# fasciaMainBoard_V0_1.net
KiCad netlist of a schematic drawn in EAGLE
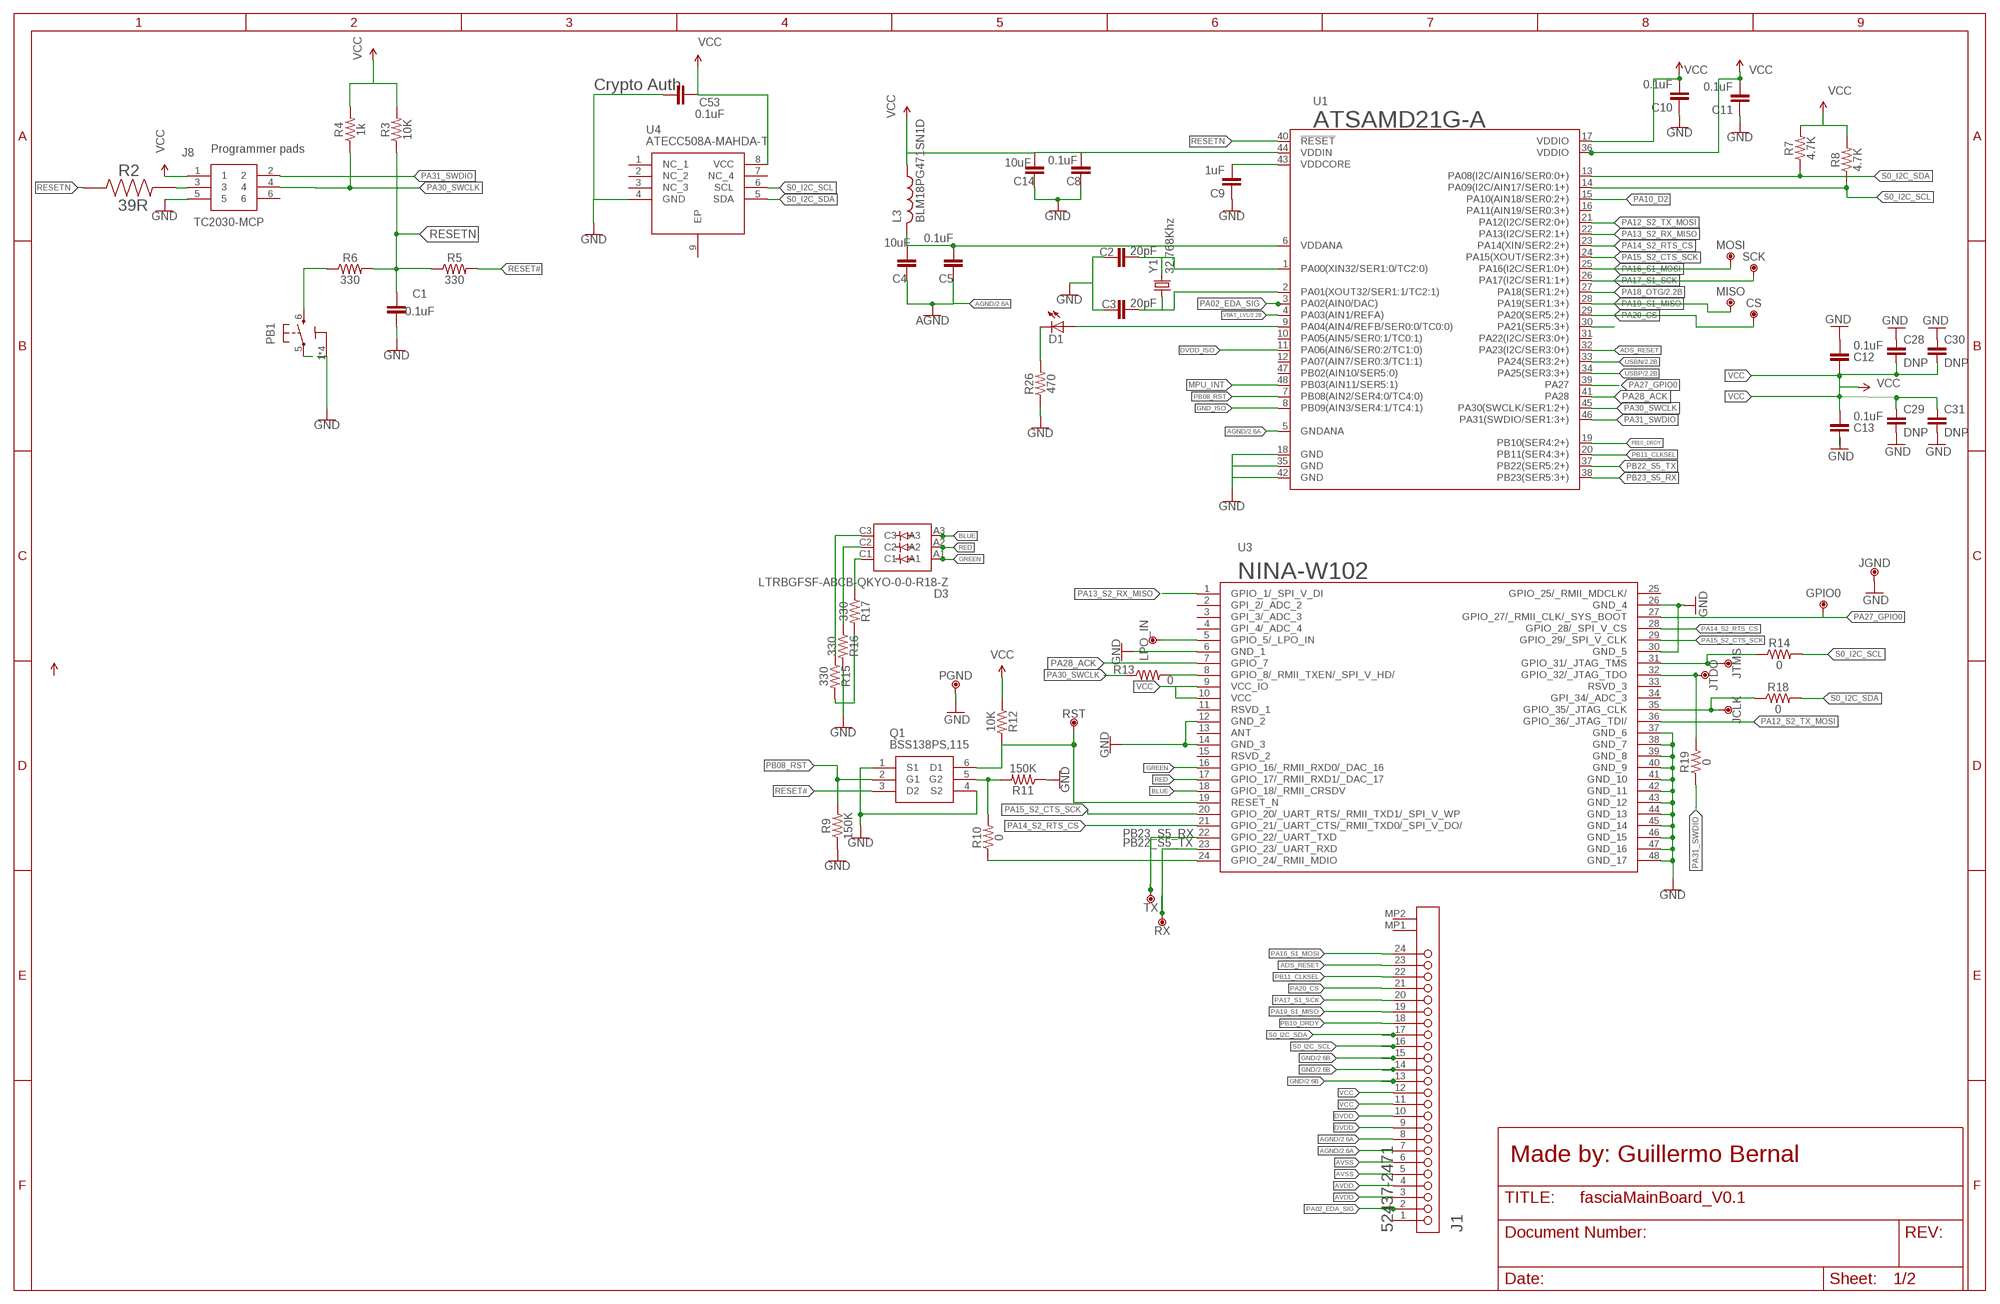
[diagram p0: schematic, sheet 1]
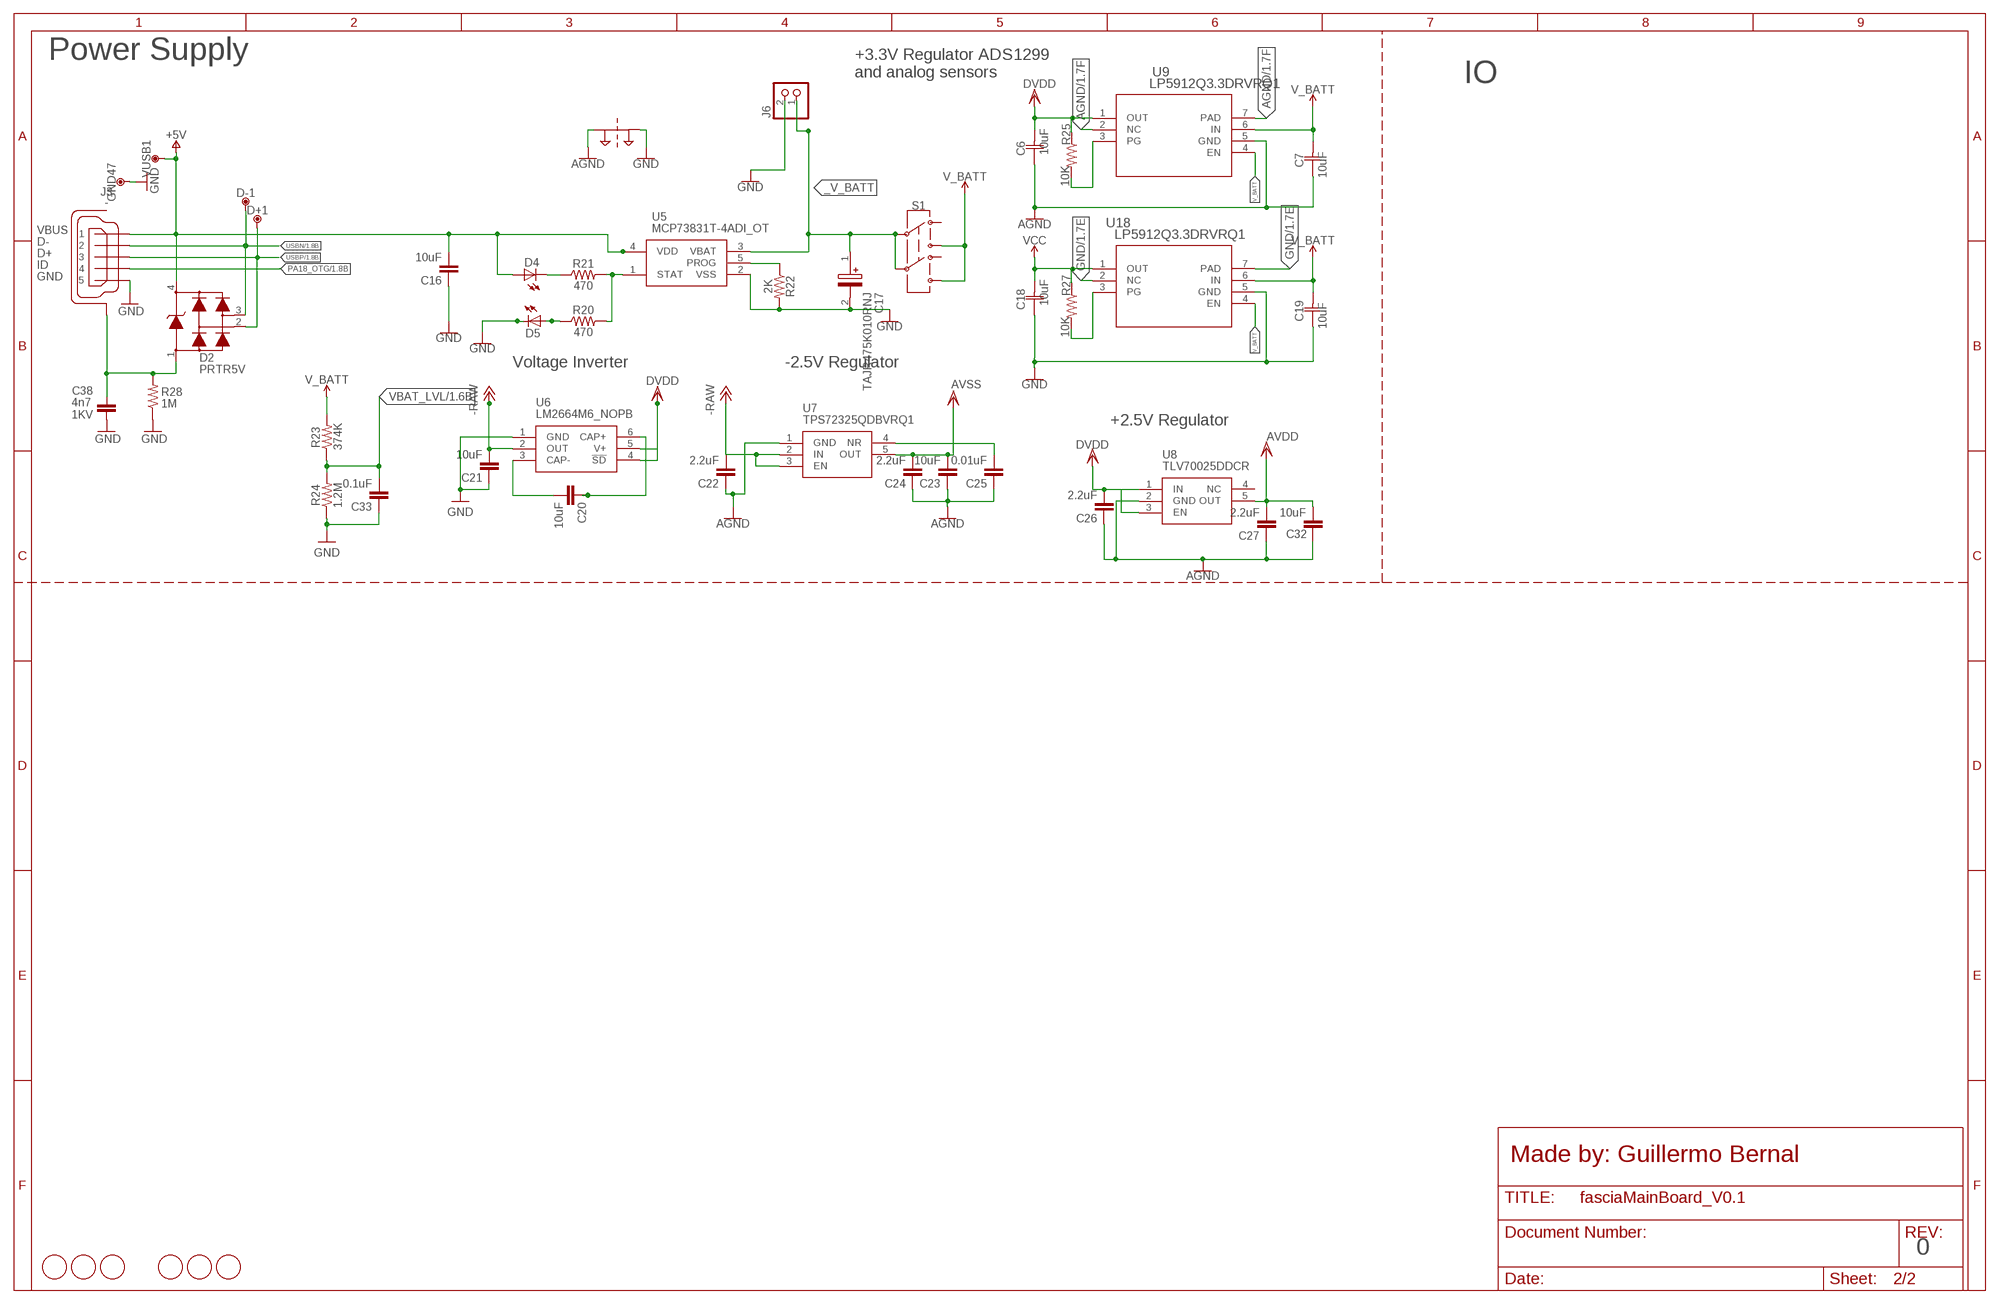
[diagram p1: schematic, sheet 2]

(export (version "E")
  (design (tool "Eeschema 10.0.6"))
  (components
    (comp (ref "C1")
      (value "0.1uF")
      (footprint "eagle-import:0402-TIGHT")
      (libsource (lib "eagle-import") (part "0.1UF-0402T-16V-10%"))
    )
    (comp (ref "C2")
      (value "20pF")
      (footprint "eagle-import:0402-TIGHT")
      (libsource (lib "eagle-import") (part "20PF-0402T-16V-10%"))
    )
    (comp (ref "C3")
      (value "20pF")
      (footprint "eagle-import:0402-TIGHT")
      (libsource (lib "eagle-import") (part "20PF-0402T-16V-10%"))
    )
    (comp (ref "C4")
      (value "10uF")
      (footprint "eagle-import:0603")
      (libsource (lib "eagle-import") (part "SparkFun-Capacitors_510_10UF-0603-6.3V-20%"))
    )
    (comp (ref "C5")
      (value "0.1uF")
      (footprint "eagle-import:0402-TIGHT")
      (libsource (lib "eagle-import") (part "0.1UF-0402T-16V-10%"))
    )
    (comp (ref "C8")
      (value "0.1uF")
      (footprint "eagle-import:0402-TIGHT")
      (libsource (lib "eagle-import") (part "0.1UF-0402T-16V-10%"))
    )
    (comp (ref "C9")
      (value "1uF")
      (footprint "eagle-import:0402-TIGHT")
      (libsource (lib "eagle-import") (part "1UF-0402T-16V-10%"))
    )
    (comp (ref "C10")
      (value "0.1uF")
      (footprint "eagle-import:0402-TIGHT")
      (libsource (lib "eagle-import") (part "0.1UF-0402T-16V-10%"))
    )
    (comp (ref "C11")
      (value "0.1uF")
      (footprint "eagle-import:0402-TIGHT")
      (libsource (lib "eagle-import") (part "0.1UF-0402T-16V-10%"))
    )
    (comp (ref "C12")
      (value "0.1uF")
      (footprint "eagle-import:0402-TIGHT")
      (libsource (lib "eagle-import") (part "0.1UF-0402T-16V-10%"))
    )
    (comp (ref "C13")
      (value "0.1uF")
      (footprint "eagle-import:0402-TIGHT")
      (libsource (lib "eagle-import") (part "0.1UF-0402T-16V-10%"))
    )
    (comp (ref "C14")
      (value "10uF")
      (footprint "eagle-import:0603")
      (libsource (lib "eagle-import") (part "SparkFun-Capacitors_510_10UF-0603-6.3V-20%"))
    )
    (comp (ref "C28")
      (value "DNP")
      (footprint "eagle-import:0402-1005X55N")
      (libsource (lib "eagle-import") (part "C-0402DNP"))
    )
    (comp (ref "C29")
      (value "DNP")
      (footprint "eagle-import:0402-1005X55N")
      (libsource (lib "eagle-import") (part "C-0402DNP"))
    )
    (comp (ref "C30")
      (value "DNP")
      (footprint "eagle-import:0603-1608X90N")
      (libsource (lib "eagle-import") (part "C-0603-DNP"))
    )
    (comp (ref "C31")
      (value "DNP")
      (footprint "eagle-import:0603-1608X90N")
      (libsource (lib "eagle-import") (part "C-0603-DNP"))
    )
    (comp (ref "C53")
      (value "0.1uF")
      (footprint "eagle-import:0402-TIGHT")
      (libsource (lib "eagle-import") (part "0.1UF-0402T-16V-10%"))
    )
    (comp (ref "CS")
      (value "DNP")
      (footprint "eagle-import:TP-0.8MM")
      (libsource (lib "eagle-import") (part "TPTP-0.8MM"))
    )
    (comp (ref "D1")
      (value "LEDCHIPLED_0603")
      (footprint "eagle-import:CHIPLED_0603")
      (libsource (lib "eagle-import") (part "LEDCHIPLED_0603"))
    )
    (comp (ref "D3")
      (value "LTRBGFSF-ABCB-QKYO-0-0-R18-Z")
      (footprint "eagle-import:PLCC-6")
      (libsource (lib "eagle-import") (part "LTRBGFSF-ABCB-QKYO-0-0-R18-Z"))
    )
    (comp (ref "GPIO0")
      (value "DNP")
      (footprint "eagle-import:TP-0.8MM")
      (libsource (lib "eagle-import") (part "TPTP-0.8MM"))
    )
    (comp (ref "J1")
      (value "MOLEX_52437-2471MOLEX_52437-2471_0_0")
      (footprint "eagle-import:MOLEX_52437-2471_0")
      (fields (field (name "MF") "Molex") (field (name "MPN") "52437-2471"))
      (libsource (lib "eagle-import") (part "MOLEX_52437-2471MOLEX_52437-2471_0_0"))
    )
    (comp (ref "J8")
      (value "TC2030-MCP")
      (footprint "eagle-import:TC2030MCP")
      (fields (field (name "MOUSER_PART_NUMBER") "579-TC2030-MCP") (field (name "RS_PART_NUMBER") "8252568"))
      (libsource (lib "eagle-import") (part "TC2030-MCP"))
    )
    (comp (ref "JCLK")
      (value "DNP")
      (footprint "eagle-import:TP-0.8MM")
      (libsource (lib "eagle-import") (part "TPTP-0.8MM"))
    )
    (comp (ref "JGND")
      (value "DNP")
      (footprint "eagle-import:TP-0.8MM")
      (libsource (lib "eagle-import") (part "TPTP-0.8MM"))
    )
    (comp (ref "JTDO")
      (value "DNP")
      (footprint "eagle-import:TP-0.8MM")
      (libsource (lib "eagle-import") (part "TPTP-0.8MM"))
    )
    (comp (ref "JTMS")
      (value "DNP")
      (footprint "eagle-import:TP-0.8MM")
      (libsource (lib "eagle-import") (part "TPTP-0.8MM"))
    )
    (comp (ref "L3")
      (value "BLM18PG471SN1D")
      (footprint "eagle-import:BEADC1608X95N")
      (fields
        (field (name "MOUSER_PART_NUMBER") "81-BLM18PG471SN1D")
        (field (name "RS_PART_NUMBER") "7241425P")
      )
      (libsource (lib "eagle-import") (part "BLM18PG471SN1D"))
    )
    (comp (ref "LPO_IN")
      (value "DNP")
      (footprint "eagle-import:TP-0.8MM")
      (libsource (lib "eagle-import") (part "TPTP-0.8MM"))
    )
    (comp (ref "MISO")
      (value "DNP")
      (footprint "eagle-import:TP-0.8MM")
      (libsource (lib "eagle-import") (part "TPTP-0.8MM"))
    )
    (comp (ref "MOSI")
      (value "DNP")
      (footprint "eagle-import:TP-0.8MM")
      (libsource (lib "eagle-import") (part "TPTP-0.8MM"))
    )
    (comp (ref "PB1")
      (value "PTS820")
      (footprint "eagle-import:C&K_PTS820_NO_HOLES")
      (fields (field (name "MANUFACTURER") "C&K"))
      (libsource (lib "eagle-import") (part "TACTILE1PTS820-NH"))
    )
    (comp (ref "PGND")
      (value "DNP")
      (footprint "eagle-import:TP-0.8MM")
      (libsource (lib "eagle-import") (part "TPTP-0.8MM"))
    )
    (comp (ref "Q1")
      (value "BSS138PS,115")
      (footprint "eagle-import:SOT65P210X110-6N")
      (fields
        (field (name "MOUSER_PART_NUMBER") "771-BSS138PS115")
        (field (name "RS_PART_NUMBER") "7920901P")
      )
      (libsource (lib "eagle-import") (part "BSS138PS,115"))
    )
    (comp (ref "R2")
      (value "39R")
      (footprint "eagle-import:RESC1005X40N")
      (fields (field (name "MF") "Yageo") (field (name "MP") "RC0402FR-0739RL"))
      (libsource (lib "eagle-import") (part "RC0402FR-0739RL"))
    )
    (comp (ref "R3")
      (value "10K")
      (footprint "eagle-import:0402-TIGHT")
      (libsource (lib "eagle-import") (part "10K"))
    )
    (comp (ref "R4")
      (value "1k")
      (footprint "eagle-import:0402-TIGHT")
      (libsource (lib "eagle-import") (part "1K"))
    )
    (comp (ref "R5")
      (value "330")
      (footprint "eagle-import:0402-TIGHT")
      (libsource (lib "eagle-import") (part "330"))
    )
    (comp (ref "R6")
      (value "330")
      (footprint "eagle-import:0402-TIGHT")
      (libsource (lib "eagle-import") (part "330"))
    )
    (comp (ref "R7")
      (value "4.7K")
      (footprint "eagle-import:0402-TIGHT")
      (libsource (lib "eagle-import") (part "4.7K"))
    )
    (comp (ref "R8")
      (value "4.7K")
      (footprint "eagle-import:0402-TIGHT")
      (libsource (lib "eagle-import") (part "4.7K"))
    )
    (comp (ref "R9")
      (value "150K")
      (footprint "eagle-import:0402-TIGHT")
      (libsource (lib "eagle-import") (part "100K"))
    )
    (comp (ref "R10")
      (value "0")
      (footprint "eagle-import:0402-TIGHT")
      (libsource (lib "eagle-import") (part "0"))
    )
    (comp (ref "R11")
      (value "150K")
      (footprint "eagle-import:0402-TIGHT")
      (libsource (lib "eagle-import") (part "100K"))
    )
    (comp (ref "R12")
      (value "10K")
      (footprint "eagle-import:0402-TIGHT")
      (libsource (lib "eagle-import") (part "10K"))
    )
    (comp (ref "R13")
      (value "0")
      (footprint "eagle-import:0402-TIGHT")
      (libsource (lib "eagle-import") (part "0"))
    )
    (comp (ref "R14")
      (value "0")
      (footprint "eagle-import:0402-TIGHT")
      (libsource (lib "eagle-import") (part "0"))
    )
    (comp (ref "R15")
      (value "330")
      (footprint "eagle-import:0402-TIGHT")
      (libsource (lib "eagle-import") (part "330"))
    )
    (comp (ref "R16")
      (value "330")
      (footprint "eagle-import:0402-TIGHT")
      (libsource (lib "eagle-import") (part "330"))
    )
    (comp (ref "R17")
      (value "330")
      (footprint "eagle-import:0402-TIGHT")
      (libsource (lib "eagle-import") (part "330"))
    )
    (comp (ref "R18")
      (value "0")
      (footprint "eagle-import:0402-TIGHT")
      (libsource (lib "eagle-import") (part "0"))
    )
    (comp (ref "R19")
      (value "0")
      (footprint "eagle-import:0402-TIGHT")
      (libsource (lib "eagle-import") (part "0"))
    )
    (comp (ref "R26")
      (value "470")
      (footprint "eagle-import:0402-TIGHT")
      (libsource (lib "eagle-import") (part "470"))
    )
    (comp (ref "RST")
      (value "DNP")
      (footprint "eagle-import:TP-0.8MM")
      (libsource (lib "eagle-import") (part "TPTP-0.8MM"))
    )
    (comp (ref "RX")
      (value "DNP")
      (footprint "eagle-import:TP-0.8MM")
      (libsource (lib "eagle-import") (part "TPTP-0.8MM"))
    )
    (comp (ref "SCK")
      (value "DNP")
      (footprint "eagle-import:TP-0.8MM")
      (libsource (lib "eagle-import") (part "TPTP-0.8MM"))
    )
    (comp (ref "TX")
      (value "DNP")
      (footprint "eagle-import:TP-0.8MM")
      (libsource (lib "eagle-import") (part "TPTP-0.8MM"))
    )
    (comp (ref "U1")
      (value "ATSAMD21G-A")
      (footprint "eagle-import:TQFP-48")
      (libsource (lib "eagle-import") (part "ATSAMD21G-A"))
    )
    (comp (ref "U3")
      (value "NINA-W102")
      (footprint "eagle-import:NINAW102")
      (libsource (lib "eagle-import") (part "NINA-W102"))
    )
    (comp (ref "U4")
      (value "ATECC508A-MAHDA-T")
      (footprint "eagle-import:SON50P300X200X60-9N")
      (fields
        (field (name "MOUSER_PART_NUMBER") "556-ATECC508A-MAHDAT")
        (field (name "RS_PART_NUMBER") "1773144P")
      )
      (libsource (lib "eagle-import") (part "ATECC508A-MAHDA-T"))
    )
    (comp (ref "Y1")
      (value "32.768Khz")
      (footprint "eagle-import:ECX-31B")
      (fields
        (field (name "MANUFACTURER_PART_NUMBER") "ECS-.327-12.5-34B-TR")
        (field (name "MOUSER_PART_NUMBER") "520-327-12.5-34B")
      )
      (libsource (lib "eagle-import") (part "ECS-.327-12.5-34B-TR"))
    )
    (comp (ref "C6")
      (value "10uF")
      (footprint "eagle-import:CAP_CL10-L")
      (fields (field (name "MANUFACTURER_PART_NUMBER") "CL10B106MQ8NRNC"))
      (libsource (lib "eagle-import") (part "CL10B106MQ8NRNCCAP_CL10-L"))
    )
    (comp (ref "C7")
      (value "10uF")
      (footprint "eagle-import:CAP_CL10-L")
      (fields (field (name "MANUFACTURER_PART_NUMBER") "CL10B106MQ8NRNC"))
      (libsource (lib "eagle-import") (part "CL10B106MQ8NRNCCAP_CL10-L"))
    )
    (comp (ref "C16")
      (value "10uF")
      (footprint "eagle-import:0603")
      (libsource (lib "eagle-import") (part "10UF-0603-6.3V-20%"))
    )
    (comp (ref "C17")
      (value "TAJR475K010RNJ")
      (footprint "eagle-import:CAPPM2014X120N")
      (fields
        (field (name "MOUSER_PART_NUMBER") "581-TAJR475K010R")
        (field (name "RS_PART_NUMBER") "1355409P")
      )
      (libsource (lib "eagle-import") (part "TAJR475K010RNJ"))
    )
    (comp (ref "C18")
      (value "10uF")
      (footprint "eagle-import:CAP_CL10-L")
      (fields (field (name "MANUFACTURER_PART_NUMBER") "CL10B106MQ8NRNC"))
      (libsource (lib "eagle-import") (part "CL10B106MQ8NRNCCAP_CL10-L"))
    )
    (comp (ref "C19")
      (value "10uF")
      (footprint "eagle-import:CAP_CL10-L")
      (fields (field (name "MANUFACTURER_PART_NUMBER") "CL10B106MQ8NRNC"))
      (libsource (lib "eagle-import") (part "CL10B106MQ8NRNCCAP_CL10-L"))
    )
    (comp (ref "C20")
      (value "10uF")
      (footprint "eagle-import:0603")
      (libsource (lib "eagle-import") (part "10UF-0603-6.3V-20%"))
    )
    (comp (ref "C21")
      (value "10uF")
      (footprint "eagle-import:0603")
      (libsource (lib "eagle-import") (part "10UF-0603-6.3V-20%"))
    )
    (comp (ref "C22")
      (value "2.2uF")
      (footprint "eagle-import:0402-TIGHT")
      (libsource (lib "eagle-import") (part "2.2UF-0402T-16V-10%"))
    )
    (comp (ref "C23")
      (value "10uF")
      (footprint "eagle-import:0603")
      (libsource (lib "eagle-import") (part "10UF-0603-6.3V-20%"))
    )
    (comp (ref "C24")
      (value "2.2uF")
      (footprint "eagle-import:0402-TIGHT")
      (libsource (lib "eagle-import") (part "2.2UF-0402T-16V-10%"))
    )
    (comp (ref "C25")
      (value "0.01uF")
      (footprint "eagle-import:0402-TIGHT")
      (libsource (lib "eagle-import") (part "0.01UF-0402T-16V-10%"))
    )
    (comp (ref "C26")
      (value "2.2uF")
      (footprint "eagle-import:0402-TIGHT")
      (libsource (lib "eagle-import") (part "2.2UF-0402T-16V-10%"))
    )
    (comp (ref "C27")
      (value "2.2uF")
      (footprint "eagle-import:0402-TIGHT")
      (libsource (lib "eagle-import") (part "2.2UF-0402T-16V-10%"))
    )
    (comp (ref "C32")
      (value "10uF")
      (footprint "eagle-import:0603")
      (libsource (lib "eagle-import") (part "10UF-0603-6.3V-20%"))
    )
    (comp (ref "C33")
      (value "0.1uF")
      (footprint "eagle-import:0402-TIGHT")
      (libsource (lib "eagle-import") (part "0.1UF-0402T-16V-10%"))
    )
    (comp (ref "C38")
      (value "4n7")
      (footprint "eagle-import:0805-R2013X50N")
      (fields (field (name "MANUFACTURER") "Kemet") (field (name "VOLTAGE") "1KV"))
      (libsource (lib "eagle-import") (part "C-08054.7NF"))
    )
    (comp (ref "D+1")
      (value "DNP")
      (footprint "eagle-import:TP-1.00MM")
      (libsource (lib "eagle-import") (part "TPTP-1.00MM"))
    )
    (comp (ref "D-1")
      (value "DNP")
      (footprint "eagle-import:TP-1.00MM")
      (libsource (lib "eagle-import") (part "TPTP-1.00MM"))
    )
    (comp (ref "D2")
      (value "PRTR5V")
      (footprint "eagle-import:SOT190P230X110-4N")
      (fields (field (name "MANUFACTURER") "NXP"))
      (libsource (lib "eagle-import") (part "PRTR5V0U2X,215"))
    )
    (comp (ref "D4")
      (value "LEDCHIPLED_0603")
      (footprint "eagle-import:CHIPLED_0603")
      (libsource (lib "eagle-import") (part "LEDCHIPLED_0603"))
    )
    (comp (ref "D5")
      (value "LEDCHIPLED_0603")
      (footprint "eagle-import:CHIPLED_0603")
      (libsource (lib "eagle-import") (part "LEDCHIPLED_0603"))
    )
    (comp (ref "FD1")
      (value "DNP")
      (footprint "eagle-import:FD-1-1.5")
      (libsource (lib "eagle-import") (part "FIDUCIAL-1.5MM"))
    )
    (comp (ref "FD2")
      (value "DNP")
      (footprint "eagle-import:FD-1-1.5")
      (libsource (lib "eagle-import") (part "FIDUCIAL-1.5MM"))
    )
    (comp (ref "FD3")
      (value "DNP")
      (footprint "eagle-import:FD-1-1.5")
      (libsource (lib "eagle-import") (part "FIDUCIAL-1.5MM"))
    )
    (comp (ref "FD4")
      (value "DNP")
      (footprint "eagle-import:FD-1-1.5")
      (libsource (lib "eagle-import") (part "FIDUCIAL-1.5MM"))
    )
    (comp (ref "FD5")
      (value "DNP")
      (footprint "eagle-import:FD-1-1.5")
      (libsource (lib "eagle-import") (part "FIDUCIAL-1.5MM"))
    )
    (comp (ref "FD6")
      (value "DNP")
      (footprint "eagle-import:FD-1-1.5")
      (libsource (lib "eagle-import") (part "FIDUCIAL-1.5MM"))
    )
    (comp (ref "GND47")
      (value "DNP")
      (footprint "eagle-import:TP-1.00MM")
      (libsource (lib "eagle-import") (part "TPTP-1.00MM"))
    )
    (comp (ref "J3")
      (value "-")
      (footprint "eagle-import:ZX62-AB-5PA")
      (fields (field (name "MANUFACTURER") "Hirose"))
      (libsource (lib "eagle-import") (part "USB-MICRO"))
    )
    (comp (ref "J6")
      (value "JST_2PIN-SMT-RA")
      (footprint "eagle-import:JST-PH-2-SMT-RA")
      (libsource (lib "eagle-import") (part "JST_2PIN-SMT-RA"))
    )
    (comp (ref "R20")
      (value "470")
      (footprint "eagle-import:0402-TIGHT")
      (libsource (lib "eagle-import") (part "470"))
    )
    (comp (ref "R21")
      (value "470")
      (footprint "eagle-import:0402-TIGHT")
      (libsource (lib "eagle-import") (part "470"))
    )
    (comp (ref "R22")
      (value "2K")
      (footprint "eagle-import:0402-TIGHT")
      (libsource (lib "eagle-import") (part "2K"))
    )
    (comp (ref "R23")
      (value "374K")
      (footprint "eagle-import:0402-TIGHT")
      (libsource (lib "eagle-import") (part "374K"))
    )
    (comp (ref "R24")
      (value "1.2M")
      (footprint "eagle-import:0402")
      (libsource (lib "eagle-import") (part "1.2M-0402-1/10W-1%"))
    )
    (comp (ref "R25")
      (value "10K")
      (footprint "eagle-import:0402-TIGHT")
      (libsource (lib "eagle-import") (part "10K"))
    )
    (comp (ref "R27")
      (value "10K")
      (footprint "eagle-import:0402-TIGHT")
      (libsource (lib "eagle-import") (part "10K"))
    )
    (comp (ref "R28")
      (value "1M")
      (footprint "eagle-import:0402-TIGHT")
      (libsource (lib "eagle-import") (part "1M"))
    )
    (comp (ref "S1")
      (value "SWITCH-DPDT-SMD-AYZ0202")
      (footprint "eagle-import:SWITCH_DPDT_SMD_AYZ0202")
      (libsource (lib "eagle-import") (part "SWITCH-DPDT-SMD-AYZ0202"))
    )
    (comp (ref "SUPPLY1")
      (value "2PT_GND_TIE")
      (footprint "eagle-import:2PT_GND_TIE")
      (libsource (lib "eagle-import") (part "2PT_GND_TIE"))
    )
    (comp (ref "U5")
      (value "MCP73831T-4ADI_OT")
      (footprint "eagle-import:SOT95P270X145-5N")
      (fields
        (field (name "MANUFACTURER_PART_NUMBER") "MCP73831T-4ADI/OT")
        (field (name "MOUSER_PART_NUMBER") "579-MCP73831T4ADIOT")
      )
      (libsource (lib "eagle-import") (part "MCP73831T-4ADI_OT"))
    )
    (comp (ref "U6")
      (value "LM2664M6_NOPB")
      (footprint "eagle-import:SOT95P280X145-6N")
      (fields
        (field (name "MANUFACTURER_PART_NUMBER") "LM2664M6/NOPB")
        (field (name "MOUSER_PART_NUMBER") "926-LM2664M6/NOPB")
        (field (name "RS_PART_NUMBER") "5358792P")
      )
      (libsource (lib "eagle-import") (part "LM2664M6_NOPB"))
    )
    (comp (ref "U7")
      (value "TPS72325QDBVRQ1")
      (footprint "eagle-import:SOT96P230X110-5N")
      (libsource (lib "eagle-import") (part "TPS72325QDBVRQ1"))
    )
    (comp (ref "U8")
      (value "TLV70025DDCR")
      (footprint "eagle-import:SOT95P280X110-5N")
      (fields (field (name "MOUSER_PART_NUMBER") "595-TLV70025DDCR"))
      (libsource (lib "eagle-import") (part "TLV70025DDCR"))
    )
    (comp (ref "U9")
      (value "LP5912Q3.3DRVRQ1")
      (footprint "eagle-import:DRV0006A")
      (libsource (lib "eagle-import") (part "LP5912Q3.3DRVRQ1"))
    )
    (comp (ref "U18")
      (value "LP5912Q3.3DRVRQ1")
      (footprint "eagle-import:DRV0006A")
      (libsource (lib "eagle-import") (part "LP5912Q3.3DRVRQ1"))
    )
    (comp (ref "VUSB1")
      (value "DNP")
      (footprint "eagle-import:TP-1.00MM")
      (libsource (lib "eagle-import") (part "TPTP-1.00MM"))
    )
  )
  (nets
    (net (code "1") (name "+5V") (class "Default")
      (node (ref "C16") (pin "2") (pinfunction "2_2") (pintype "passive"))
      (node (ref "D2") (pin "4") (pinfunction "4_4") (pintype "passive"))
      (node (ref "D4") (pin "A") (pinfunction "A_A") (pintype "passive"))
      (node (ref "J3") (pin "1") (pinfunction "1_1") (pintype "passive"))
      (node (ref "U5") (pin "4") (pinfunction "VDD_4") (pintype "bidirectional"))
      (node (ref "VUSB1") (pin "X") (pinfunction "P$1_X") (pintype "passive"))
    )
    (net (code "2") (name "-RAW") (class "Default")
      (node (ref "C21") (pin "2") (pinfunction "2_2") (pintype "passive"))
      (node (ref "C22") (pin "2") (pinfunction "2_2") (pintype "passive"))
      (node (ref "U6") (pin "2") (pinfunction "OUT_2") (pintype "output"))
      (node (ref "U7") (pin "2") (pinfunction "IN_2") (pintype "power_in"))
      (node (ref "U7") (pin "3") (pinfunction "EN_3") (pintype "bidirectional"))
    )
    (net (code "3") (name "ADS_RESET") (class "Default")
      (node (ref "J1") (pin "23") (pinfunction "23_23") (pintype "passive"))
      (node (ref "U1") (pin "32") (pinfunction "PA23(I2C/SER3:0+)_32") (pintype "bidirectional"))
    )
    (net (code "4") (name "AGND") (class "Default")
      (node (ref "C22") (pin "1") (pinfunction "1_1") (pintype "passive"))
      (node (ref "C23") (pin "1") (pinfunction "1_1") (pintype "passive"))
      (node (ref "C24") (pin "1") (pinfunction "1_1") (pintype "passive"))
      (node (ref "C25") (pin "1") (pinfunction "1_1") (pintype "passive"))
      (node (ref "C26") (pin "1") (pinfunction "1_1") (pintype "passive"))
      (node (ref "C27") (pin "1") (pinfunction "1_1") (pintype "passive"))
      (node (ref "C32") (pin "1") (pinfunction "1_1") (pintype "passive"))
      (node (ref "C4") (pin "1") (pinfunction "1_1") (pintype "passive"))
      (node (ref "C5") (pin "1") (pinfunction "1_1") (pintype "passive"))
      (node (ref "C6") (pin "1") (pinfunction "1_1") (pintype "passive"))
      (node (ref "C7") (pin "1") (pinfunction "1_1") (pintype "passive"))
      (node (ref "J1") (pin "7") (pinfunction "7_7") (pintype "passive"))
      (node (ref "J1") (pin "8") (pinfunction "8_8") (pintype "passive"))
      (node (ref "SUPPLY1") (pin "P$1") (pinfunction "P$1_P$1") (pintype "bidirectional"))
      (node (ref "U1") (pin "5") (pinfunction "GNDANA_5") (pintype "bidirectional"))
      (node (ref "U7") (pin "1") (pinfunction "GND_1") (pintype "power_in"))
      (node (ref "U8") (pin "2") (pinfunction "GND_2") (pintype "bidirectional"))
      (node (ref "U9") (pin "2") (pinfunction "NC_2") (pintype "passive"))
      (node (ref "U9") (pin "5") (pinfunction "GND_5") (pintype "power_in"))
      (node (ref "U9") (pin "7") (pinfunction "PAD_7") (pintype "power_in"))
    )
    (net (code "5") (name "AVDD") (class "Default")
      (node (ref "C27") (pin "2") (pinfunction "2_2") (pintype "passive"))
      (node (ref "C32") (pin "2") (pinfunction "2_2") (pintype "passive"))
      (node (ref "J1") (pin "3") (pinfunction "3_3") (pintype "passive"))
      (node (ref "J1") (pin "4") (pinfunction "4_4") (pintype "passive"))
      (node (ref "U8") (pin "5") (pinfunction "OUT_5") (pintype "bidirectional"))
    )
    (net (code "6") (name "AVSS") (class "Default")
      (node (ref "C23") (pin "2") (pinfunction "2_2") (pintype "passive"))
      (node (ref "C24") (pin "2") (pinfunction "2_2") (pintype "passive"))
      (node (ref "J1") (pin "5") (pinfunction "5_5") (pintype "passive"))
      (node (ref "J1") (pin "6") (pinfunction "6_6") (pintype "passive"))
      (node (ref "U7") (pin "5") (pinfunction "OUT_5") (pintype "power_in"))
    )
    (net (code "7") (name "BLUE") (class "Default")
      (node (ref "D3") (pin "A3") (pinfunction "A3_A3") (pintype "bidirectional"))
      (node (ref "U3") (pin "18") (pinfunction "GPIO_18/_RMII_CRSDV_18") (pintype "bidirectional"))
    )
    (net (code "8") (name "DVDD") (class "Default")
      (node (ref "C26") (pin "2") (pinfunction "2_2") (pintype "passive"))
      (node (ref "C6") (pin "2") (pinfunction "2_2") (pintype "passive"))
      (node (ref "J1") (pin "10") (pinfunction "10_10") (pintype "passive"))
      (node (ref "J1") (pin "9") (pinfunction "9_9") (pintype "passive"))
      (node (ref "R25") (pin "1") (pinfunction "1_1") (pintype "passive"))
      (node (ref "U6") (pin "4") (pinfunction "~{SD}_4") (pintype "input"))
      (node (ref "U6") (pin "5") (pinfunction "V+_5") (pintype "power_in"))
      (node (ref "U8") (pin "1") (pinfunction "IN_1") (pintype "bidirectional"))
      (node (ref "U8") (pin "3") (pinfunction "EN_3") (pintype "bidirectional"))
      (node (ref "U9") (pin "1") (pinfunction "OUT_1") (pintype "power_in"))
    )
    (net (code "9") (name "DVDD_ISO") (class "Default")
      (node (ref "U1") (pin "11") (pinfunction "PA06(AIN6/SER0:2/TC1:0)_11") (pintype "bidirectional"))
    )
    (net (code "10") (name "GND") (class "Default")
      (node (ref "C1") (pin "2") (pinfunction "2_2") (pintype "passive"))
      (node (ref "C10") (pin "1") (pinfunction "1_1") (pintype "passive"))
      (node (ref "C11") (pin "1") (pinfunction "1_1") (pintype "passive"))
      (node (ref "C12") (pin "2") (pinfunction "2_2") (pintype "passive"))
      (node (ref "C13") (pin "1") (pinfunction "1_1") (pintype "passive"))
      (node (ref "C14") (pin "1") (pinfunction "1_1") (pintype "passive"))
      (node (ref "C16") (pin "1") (pinfunction "1_1") (pintype "passive"))
      (node (ref "C17") (pin "2") (pinfunction "-_2") (pintype "bidirectional"))
      (node (ref "C18") (pin "1") (pinfunction "1_1") (pintype "passive"))
      (node (ref "C19") (pin "1") (pinfunction "1_1") (pintype "passive"))
      (node (ref "C2") (pin "1") (pinfunction "1_1") (pintype "passive"))
      (node (ref "C21") (pin "1") (pinfunction "1_1") (pintype "passive"))
      (node (ref "C28") (pin "1") (pinfunction "1_1") (pintype "passive"))
      (node (ref "C29") (pin "2") (pinfunction "2_2") (pintype "passive"))
      (node (ref "C3") (pin "1") (pinfunction "1_1") (pintype "passive"))
      (node (ref "C30") (pin "1") (pinfunction "1_1") (pintype "passive"))
      (node (ref "C31") (pin "2") (pinfunction "2_2") (pintype "passive"))
      (node (ref "C33") (pin "1") (pinfunction "1_1") (pintype "passive"))
      (node (ref "C38") (pin "2") (pinfunction "2_2") (pintype "passive"))
      (node (ref "C53") (pin "2") (pinfunction "2_2") (pintype "passive"))
      (node (ref "C8") (pin "1") (pinfunction "1_1") (pintype "passive"))
      (node (ref "C9") (pin "1") (pinfunction "1_1") (pintype "passive"))
      (node (ref "D5") (pin "C") (pinfunction "C_C") (pintype "passive"))
      (node (ref "GND47") (pin "X") (pinfunction "P$1_X") (pintype "passive"))
      (node (ref "J1") (pin "13") (pinfunction "13_13") (pintype "passive"))
      (node (ref "J1") (pin "14") (pinfunction "14_14") (pintype "passive"))
      (node (ref "J1") (pin "15") (pinfunction "15_15") (pintype "passive"))
      (node (ref "J3") (pin "5") (pinfunction "5_5") (pintype "passive"))
      (node (ref "J6") (pin "2") (pinfunction "1_2") (pintype "passive"))
      (node (ref "J8") (pin "5") (pinfunction "5_5") (pintype "bidirectional"))
      (node (ref "JGND") (pin "X") (pinfunction "P$1_X") (pintype "passive"))
      (node (ref "PB1") (pin "1") (pinfunction "3_1") (pintype "power_in"))
      (node (ref "PB1") (pin "2") (pinfunction "3_2") (pintype "power_in"))
      (node (ref "PB1") (pin "3") (pinfunction "3_3") (pintype "power_in"))
      (node (ref "PB1") (pin "4") (pinfunction "3_4") (pintype "power_in"))
      (node (ref "PB1") (pin "5") (pinfunction "1_5") (pintype "passive"))
      (node (ref "PGND") (pin "X") (pinfunction "P$1_X") (pintype "passive"))
      (node (ref "Q1") (pin "1") (pinfunction "S1_1") (pintype "bidirectional"))
      (node (ref "Q1") (pin "4") (pinfunction "S2_4") (pintype "bidirectional"))
      (node (ref "R11") (pin "1") (pinfunction "1_1") (pintype "passive"))
      (node (ref "R15") (pin "2") (pinfunction "2_2") (pintype "passive"))
      (node (ref "R16") (pin "2") (pinfunction "2_2") (pintype "passive"))
      (node (ref "R17") (pin "2") (pinfunction "2_2") (pintype "passive"))
      (node (ref "R22") (pin "2") (pinfunction "2_2") (pintype "passive"))
      (node (ref "R24") (pin "1") (pinfunction "1_1") (pintype "passive"))
      (node (ref "R26") (pin "1") (pinfunction "1_1") (pintype "passive"))
      (node (ref "R28") (pin "1") (pinfunction "1_1") (pintype "passive"))
      (node (ref "R9") (pin "1") (pinfunction "1_1") (pintype "passive"))
      (node (ref "SUPPLY1") (pin "P$2") (pinfunction "P$2_P$2") (pintype "bidirectional"))
      (node (ref "U1") (pin "18") (pinfunction "GND_18") (pintype "bidirectional"))
      (node (ref "U1") (pin "35") (pinfunction "GND_35") (pintype "bidirectional"))
      (node (ref "U1") (pin "42") (pinfunction "GND_42") (pintype "bidirectional"))
      (node (ref "U18") (pin "2") (pinfunction "NC_2") (pintype "passive"))
      (node (ref "U18") (pin "5") (pinfunction "GND_5") (pintype "power_in"))
      (node (ref "U18") (pin "7") (pinfunction "PAD_7") (pintype "power_in"))
      (node (ref "U3") (pin "12") (pinfunction "GND_2_12") (pintype "bidirectional"))
      (node (ref "U3") (pin "14") (pinfunction "GND_3_14") (pintype "bidirectional"))
      (node (ref "U3") (pin "26") (pinfunction "GND_4_26") (pintype "bidirectional"))
      (node (ref "U3") (pin "30") (pinfunction "GND_5_30") (pintype "bidirectional"))
      (node (ref "U3") (pin "37") (pinfunction "GND_6_37") (pintype "bidirectional"))
      (node (ref "U3") (pin "38") (pinfunction "GND_7_38") (pintype "bidirectional"))
      (node (ref "U3") (pin "39") (pinfunction "GND_8_39") (pintype "bidirectional"))
      (node (ref "U3") (pin "40") (pinfunction "GND_9_40") (pintype "bidirectional"))
      (node (ref "U3") (pin "41") (pinfunction "GND_10_41") (pintype "bidirectional"))
      (node (ref "U3") (pin "42") (pinfunction "GND_11_42") (pintype "bidirectional"))
      (node (ref "U3") (pin "43") (pinfunction "GND_12_43") (pintype "bidirectional"))
      (node (ref "U3") (pin "44") (pinfunction "GND_13_44") (pintype "bidirectional"))
      (node (ref "U3") (pin "45") (pinfunction "GND_14_45") (pintype "bidirectional"))
      (node (ref "U3") (pin "46") (pinfunction "GND_15_46") (pintype "bidirectional"))
      (node (ref "U3") (pin "47") (pinfunction "GND_16_47") (pintype "bidirectional"))
      (node (ref "U3") (pin "48") (pinfunction "GND_17_48") (pintype "bidirectional"))
      (node (ref "U3") (pin "6") (pinfunction "GND_1_6") (pintype "bidirectional"))
      (node (ref "U4") (pin "4") (pinfunction "GND_4") (pintype "bidirectional"))
      (node (ref "U5") (pin "2") (pinfunction "VSS_2") (pintype "bidirectional"))
      (node (ref "U6") (pin "1") (pinfunction "GND_1") (pintype "power_in"))
    )
    (net (code "11") (name "GND_ISO") (class "Default")
      (node (ref "U1") (pin "8") (pinfunction "PB09(AIN3/SER4:1/TC4:1)_8") (pintype "bidirectional"))
    )
    (net (code "12") (name "GREEN") (class "Default")
      (node (ref "D3") (pin "A1") (pinfunction "A1_A1") (pintype "bidirectional"))
      (node (ref "U3") (pin "16") (pinfunction "GPIO_16/_RMII_RXD0/_DAC_16_16") (pintype "bidirectional"))
    )
    (net (code "13") (name "MPU_INT") (class "Default")
      (node (ref "U1") (pin "48") (pinfunction "PB03(AIN11/SER5:1)_48") (pintype "bidirectional"))
    )
    (net (code "14") (name "Net-(C38-Pad1)") (class "Default")
      (node (ref "C38") (pin "1") (pinfunction "1_1") (pintype "passive"))
      (node (ref "D2") (pin "1") (pinfunction "1_1") (pintype "passive"))
      (node (ref "J3") (pin "10") (pinfunction "SH_10") (pintype "passive"))
      (node (ref "J3") (pin "11") (pinfunction "SH_11") (pintype "passive"))
      (node (ref "J3") (pin "6") (pinfunction "SH_6") (pintype "passive"))
      (node (ref "J3") (pin "7") (pinfunction "SH_7") (pintype "passive"))
      (node (ref "J3") (pin "8") (pinfunction "SH_8") (pintype "passive"))
      (node (ref "J3") (pin "9") (pinfunction "SH_9") (pintype "passive"))
      (node (ref "R28") (pin "2") (pinfunction "2_2") (pintype "passive"))
    )
    (net (code "15") (name "Net-(D1-PadC)") (class "Default")
      (node (ref "D1") (pin "C") (pinfunction "C_C") (pintype "passive"))
      (node (ref "R26") (pin "2") (pinfunction "2_2") (pintype "passive"))
    )
    (net (code "16") (name "Net-(D3-PadC1)") (class "Default")
      (node (ref "D3") (pin "C1") (pinfunction "C1_C1") (pintype "bidirectional"))
      (node (ref "R17") (pin "1") (pinfunction "1_1") (pintype "passive"))
    )
    (net (code "17") (name "Net-(D3-PadC2)") (class "Default")
      (node (ref "D3") (pin "C2") (pinfunction "C2_C2") (pintype "bidirectional"))
      (node (ref "R16") (pin "1") (pinfunction "1_1") (pintype "passive"))
    )
    (net (code "18") (name "Net-(D3-PadC3)") (class "Default")
      (node (ref "D3") (pin "C3") (pinfunction "C3_C3") (pintype "bidirectional"))
      (node (ref "R15") (pin "1") (pinfunction "1_1") (pintype "passive"))
    )
    (net (code "19") (name "Net-(D4-PadC)") (class "Default")
      (node (ref "D4") (pin "C") (pinfunction "C_C") (pintype "passive"))
      (node (ref "R21") (pin "1") (pinfunction "1_1") (pintype "passive"))
    )
    (net (code "20") (name "Net-(D5-PadA)") (class "Default")
      (node (ref "D5") (pin "A") (pinfunction "A_A") (pintype "passive"))
      (node (ref "R20") (pin "1") (pinfunction "1_1") (pintype "passive"))
    )
    (net (code "21") (name "Net-(J8-Pad3)") (class "Default")
      (node (ref "J8") (pin "3") (pinfunction "3_3") (pintype "bidirectional"))
      (node (ref "R2") (pin "2") (pinfunction "2_2") (pintype "passive"))
    )
    (net (code "22") (name "Net-(JCLK-P$1)") (class "Default")
      (node (ref "JCLK") (pin "X") (pinfunction "P$1_X") (pintype "passive"))
      (node (ref "R18") (pin "1") (pinfunction "1_1") (pintype "passive"))
      (node (ref "U3") (pin "35") (pinfunction "GPIO_35/_JTAG_CLK_35") (pintype "bidirectional"))
    )
    (net (code "23") (name "Net-(JTDO-P$1)") (class "Default")
      (node (ref "JTDO") (pin "X") (pinfunction "P$1_X") (pintype "passive"))
      (node (ref "R19") (pin "2") (pinfunction "2_2") (pintype "passive"))
      (node (ref "U3") (pin "32") (pinfunction "GPIO_32/_JTAG_TDO_32") (pintype "bidirectional"))
    )
    (net (code "24") (name "Net-(JTMS-P$1)") (class "Default")
      (node (ref "JTMS") (pin "X") (pinfunction "P$1_X") (pintype "passive"))
      (node (ref "R14") (pin "1") (pinfunction "1_1") (pintype "passive"))
      (node (ref "U3") (pin "31") (pinfunction "GPIO_31/_JTAG_TMS_31") (pintype "bidirectional"))
    )
    (net (code "25") (name "Net-(LPO_IN-P$1)") (class "Default")
      (node (ref "LPO_IN") (pin "X") (pinfunction "P$1_X") (pintype "passive"))
      (node (ref "U3") (pin "5") (pinfunction "GPIO_5/_LPO_IN_5") (pintype "bidirectional"))
    )
    (net (code "26") (name "Net-(PB1-2)") (class "Default")
      (node (ref "PB1") (pin "6") (pinfunction "2_6") (pintype "passive"))
      (node (ref "R6") (pin "1") (pinfunction "1_1") (pintype "passive"))
    )
    (net (code "27") (name "Net-(Q1-D1)") (class "Default")
      (node (ref "Q1") (pin "6") (pinfunction "D1_6") (pintype "bidirectional"))
      (node (ref "R12") (pin "2") (pinfunction "2_2") (pintype "passive"))
      (node (ref "RST") (pin "X") (pinfunction "P$1_X") (pintype "passive"))
      (node (ref "U3") (pin "19") (pinfunction "RESET_N_19") (pintype "bidirectional"))
    )
    (net (code "28") (name "Net-(Q1-G2)") (class "Default")
      (node (ref "Q1") (pin "5") (pinfunction "G2_5") (pintype "bidirectional"))
      (node (ref "R10") (pin "2") (pinfunction "2_2") (pintype "passive"))
      (node (ref "R11") (pin "2") (pinfunction "2_2") (pintype "passive"))
    )
    (net (code "29") (name "Net-(U1-PA00(XIN32{slash}SER1:0{slash}TC2:0))") (class "Default")
      (node (ref "C2") (pin "2") (pinfunction "2_2") (pintype "passive"))
      (node (ref "U1") (pin "1") (pinfunction "PA00(XIN32/SER1:0/TC2:0)_1") (pintype "bidirectional"))
      (node (ref "Y1") (pin "2") (pinfunction "2_2") (pintype "passive"))
    )
    (net (code "30") (name "Net-(U1-PA01(XOUT32{slash}SER1:1{slash}TC2:1))") (class "Default")
      (node (ref "C3") (pin "2") (pinfunction "2_2") (pintype "passive"))
      (node (ref "U1") (pin "2") (pinfunction "PA01(XOUT32/SER1:1/TC2:1)_2") (pintype "bidirectional"))
      (node (ref "Y1") (pin "1") (pinfunction "1_1") (pintype "passive"))
    )
    (net (code "31") (name "Net-(U1-PA04(AIN4{slash}REFB{slash}SER0:0{slash}TC0:0))") (class "Default")
      (node (ref "D1") (pin "A") (pinfunction "A_A") (pintype "passive"))
      (node (ref "U1") (pin "9") (pinfunction "PA04(AIN4/REFB/SER0:0/TC0:0)_9") (pintype "bidirectional"))
    )
    (net (code "32") (name "Net-(U1-VDDANA)") (class "Default")
      (node (ref "C4") (pin "2") (pinfunction "2_2") (pintype "passive"))
      (node (ref "C5") (pin "2") (pinfunction "2_2") (pintype "passive"))
      (node (ref "L3") (pin "2") (pinfunction "2_2") (pintype "passive"))
      (node (ref "U1") (pin "6") (pinfunction "VDDANA_6") (pintype "bidirectional"))
    )
    (net (code "33") (name "Net-(U1-VDDCORE)") (class "Default")
      (node (ref "C9") (pin "2") (pinfunction "2_2") (pintype "passive"))
      (node (ref "U1") (pin "43") (pinfunction "VDDCORE_43") (pintype "bidirectional"))
    )
    (net (code "34") (name "Net-(U3-GPIO_8{slash}_RMII_TXEN{slash}_SPI_V_HD{slash})") (class "Default")
      (node (ref "R13") (pin "2") (pinfunction "2_2") (pintype "passive"))
      (node (ref "U3") (pin "8") (pinfunction "GPIO_8/_RMII_TXEN/_SPI_V_HD/_8") (pintype "bidirectional"))
    )
    (net (code "35") (name "Net-(U3-GPIO_24{slash}_RMII_MDIO)") (class "Default")
      (node (ref "R10") (pin "1") (pinfunction "1_1") (pintype "passive"))
      (node (ref "U3") (pin "24") (pinfunction "GPIO_24/_RMII_MDIO_24") (pintype "bidirectional"))
    )
    (net (code "36") (name "Net-(U5-PROG)") (class "Default")
      (node (ref "R22") (pin "1") (pinfunction "1_1") (pintype "passive"))
      (node (ref "U5") (pin "5") (pinfunction "PROG_5") (pintype "bidirectional"))
    )
    (net (code "37") (name "Net-(U5-STAT)") (class "Default")
      (node (ref "R20") (pin "2") (pinfunction "2_2") (pintype "passive"))
      (node (ref "R21") (pin "2") (pinfunction "2_2") (pintype "passive"))
      (node (ref "U5") (pin "1") (pinfunction "STAT_1") (pintype "bidirectional"))
    )
    (net (code "38") (name "Net-(U6-CAP+)") (class "Default")
      (node (ref "C20") (pin "1") (pinfunction "1_1") (pintype "passive"))
      (node (ref "U6") (pin "6") (pinfunction "CAP+_6") (pintype "power_in"))
    )
    (net (code "39") (name "Net-(U6-CAP-)") (class "Default")
      (node (ref "C20") (pin "2") (pinfunction "2_2") (pintype "passive"))
      (node (ref "U6") (pin "3") (pinfunction "CAP-_3") (pintype "power_in"))
    )
    (net (code "40") (name "Net-(U7-NR)") (class "Default")
      (node (ref "C25") (pin "2") (pinfunction "2_2") (pintype "passive"))
      (node (ref "U7") (pin "4") (pinfunction "NR_4") (pintype "bidirectional"))
    )
    (net (code "41") (name "Net-(U9-PG)") (class "Default")
      (node (ref "R25") (pin "2") (pinfunction "2_2") (pintype "passive"))
      (node (ref "U9") (pin "3") (pinfunction "PG_3") (pintype "output"))
    )
    (net (code "42") (name "Net-(U18-PG)") (class "Default")
      (node (ref "R27") (pin "2") (pinfunction "2_2") (pintype "passive"))
      (node (ref "U18") (pin "3") (pinfunction "PG_3") (pintype "output"))
    )
    (net (code "43") (name "PA02_EDA_SIG") (class "Default")
      (node (ref "J1") (pin "2") (pinfunction "2_2") (pintype "passive"))
      (node (ref "U1") (pin "3") (pinfunction "PA02(AIN0/DAC)_3") (pintype "bidirectional"))
    )
    (net (code "44") (name "PA10_D2") (class "Default")
      (node (ref "U1") (pin "15") (pinfunction "PA10(AIN18/SER0:2+)_15") (pintype "bidirectional"))
    )
    (net (code "45") (name "PA12_S2_TX_MOSI") (class "Default")
      (node (ref "U1") (pin "21") (pinfunction "PA12(I2C/SER2:0+)_21") (pintype "bidirectional"))
      (node (ref "U3") (pin "36") (pinfunction "GPIO_36/_JTAG_TDI/_36") (pintype "bidirectional"))
    )
    (net (code "46") (name "PA13_S2_RX_MISO") (class "Default")
      (node (ref "U1") (pin "22") (pinfunction "PA13(I2C/SER2:1+)_22") (pintype "bidirectional"))
      (node (ref "U3") (pin "1") (pinfunction "GPIO_1/_SPI_V_DI_1") (pintype "bidirectional"))
    )
    (net (code "47") (name "PA14_S2_RTS_CS") (class "Default")
      (node (ref "U1") (pin "23") (pinfunction "PA14(XIN/SER2:2+)_23") (pintype "bidirectional"))
      (node (ref "U3") (pin "21") (pinfunction "GPIO_21/_UART_CTS/_RMII_TXD0/_SPI_V_DO/_21") (pintype "bidirectional"))
      (node (ref "U3") (pin "28") (pinfunction "GPIO_28/_SPI_V_CS_28") (pintype "bidirectional"))
    )
    (net (code "48") (name "PA15_S2_CTS_SCK") (class "Default")
      (node (ref "U1") (pin "24") (pinfunction "PA15(XOUT/SER2:3+)_24") (pintype "bidirectional"))
      (node (ref "U3") (pin "20") (pinfunction "GPIO_20/_UART_RTS/_RMII_TXD1/_SPI_V_WP_20") (pintype "bidirectional"))
      (node (ref "U3") (pin "29") (pinfunction "GPIO_29/_SPI_V_CLK_29") (pintype "bidirectional"))
    )
    (net (code "49") (name "PA16_S1_MOSI") (class "Default")
      (node (ref "J1") (pin "24") (pinfunction "24_24") (pintype "passive"))
      (node (ref "MOSI") (pin "X") (pinfunction "P$1_X") (pintype "passive"))
      (node (ref "U1") (pin "25") (pinfunction "PA16(I2C/SER1:0+)_25") (pintype "bidirectional"))
    )
    (net (code "50") (name "PA17_S1_SCK") (class "Default")
      (node (ref "J1") (pin "20") (pinfunction "20_20") (pintype "passive"))
      (node (ref "SCK") (pin "X") (pinfunction "P$1_X") (pintype "passive"))
      (node (ref "U1") (pin "26") (pinfunction "PA17(I2C/SER1:1+)_26") (pintype "bidirectional"))
    )
    (net (code "51") (name "PA18_OTG") (class "Default")
      (node (ref "J3") (pin "4") (pinfunction "4_4") (pintype "passive"))
      (node (ref "U1") (pin "27") (pinfunction "PA18(SER1:2+)_27") (pintype "bidirectional"))
    )
    (net (code "52") (name "PA19_S1_MISO") (class "Default")
      (node (ref "J1") (pin "19") (pinfunction "19_19") (pintype "passive"))
      (node (ref "MISO") (pin "X") (pinfunction "P$1_X") (pintype "passive"))
      (node (ref "U1") (pin "28") (pinfunction "PA19(SER1:3+)_28") (pintype "bidirectional"))
    )
    (net (code "53") (name "PA20_CS") (class "Default")
      (node (ref "CS") (pin "X") (pinfunction "P$1_X") (pintype "passive"))
      (node (ref "J1") (pin "21") (pinfunction "21_21") (pintype "passive"))
      (node (ref "U1") (pin "29") (pinfunction "PA20(SER5:2+)_29") (pintype "bidirectional"))
    )
    (net (code "54") (name "PA27_GPIO0") (class "Default")
      (node (ref "GPIO0") (pin "X") (pinfunction "P$1_X") (pintype "passive"))
      (node (ref "U1") (pin "39") (pinfunction "PA27_39") (pintype "bidirectional"))
      (node (ref "U3") (pin "27") (pinfunction "GPIO_27/_RMII_CLK/_SYS_BOOT_27") (pintype "bidirectional"))
    )
    (net (code "55") (name "PA28_ACK") (class "Default")
      (node (ref "U1") (pin "41") (pinfunction "PA28_41") (pintype "bidirectional"))
      (node (ref "U3") (pin "7") (pinfunction "GPIO_7_7") (pintype "bidirectional"))
    )
    (net (code "56") (name "PA30_SWCLK") (class "Default")
      (node (ref "J8") (pin "4") (pinfunction "4_4") (pintype "bidirectional"))
      (node (ref "R13") (pin "1") (pinfunction "1_1") (pintype "passive"))
      (node (ref "R4") (pin "1") (pinfunction "1_1") (pintype "passive"))
      (node (ref "U1") (pin "45") (pinfunction "PA30(SWCLK/SER1:2+)_45") (pintype "bidirectional"))
    )
    (net (code "57") (name "PA31_SWDIO") (class "Default")
      (node (ref "J8") (pin "2") (pinfunction "2_2") (pintype "bidirectional"))
      (node (ref "R19") (pin "1") (pinfunction "1_1") (pintype "passive"))
      (node (ref "U1") (pin "46") (pinfunction "PA31(SWDIO/SER1:3+)_46") (pintype "bidirectional"))
    )
    (net (code "58") (name "PB08_RST") (class "Default")
      (node (ref "Q1") (pin "2") (pinfunction "G1_2") (pintype "bidirectional"))
      (node (ref "R9") (pin "2") (pinfunction "2_2") (pintype "passive"))
      (node (ref "U1") (pin "7") (pinfunction "PB08(AIN2/SER4:0/TC4:0)_7") (pintype "bidirectional"))
    )
    (net (code "59") (name "PB10_DRDY") (class "Default")
      (node (ref "J1") (pin "18") (pinfunction "18_18") (pintype "passive"))
      (node (ref "U1") (pin "19") (pinfunction "PB10(SER4:2+)_19") (pintype "bidirectional"))
    )
    (net (code "60") (name "PB11_CLKSEL") (class "Default")
      (node (ref "J1") (pin "22") (pinfunction "22_22") (pintype "passive"))
      (node (ref "U1") (pin "20") (pinfunction "PB11(SER4:3+)_20") (pintype "bidirectional"))
    )
    (net (code "61") (name "PB22_S5_TX") (class "Default")
      (node (ref "RX") (pin "X") (pinfunction "P$1_X") (pintype "passive"))
      (node (ref "U1") (pin "37") (pinfunction "PB22(SER5:2+)_37") (pintype "bidirectional"))
      (node (ref "U3") (pin "23") (pinfunction "GPIO_23/_UART_RXD_23") (pintype "bidirectional"))
    )
    (net (code "62") (name "PB23_S5_RX") (class "Default")
      (node (ref "TX") (pin "X") (pinfunction "P$1_X") (pintype "passive"))
      (node (ref "U1") (pin "38") (pinfunction "PB23(SER5:3+)_38") (pintype "bidirectional"))
      (node (ref "U3") (pin "22") (pinfunction "GPIO_22/_UART_TXD_22") (pintype "bidirectional"))
    )
    (net (code "63") (name "RED") (class "Default")
      (node (ref "D3") (pin "A2") (pinfunction "A2_A2") (pintype "bidirectional"))
      (node (ref "U3") (pin "17") (pinfunction "GPIO_17/_RMII_RXD1/_DAC_17_17") (pintype "bidirectional"))
    )
    (net (code "64") (name "RESET#") (class "Default")
      (node (ref "Q1") (pin "3") (pinfunction "D2_3") (pintype "bidirectional"))
      (node (ref "R5") (pin "2") (pinfunction "2_2") (pintype "passive"))
    )
    (net (code "65") (name "RESETN") (class "Default")
      (node (ref "C1") (pin "1") (pinfunction "1_1") (pintype "passive"))
      (node (ref "R2") (pin "1") (pinfunction "1_1") (pintype "passive"))
      (node (ref "R3") (pin "1") (pinfunction "1_1") (pintype "passive"))
      (node (ref "R5") (pin "1") (pinfunction "1_1") (pintype "passive"))
      (node (ref "R6") (pin "2") (pinfunction "2_2") (pintype "passive"))
      (node (ref "U1") (pin "40") (pinfunction "~{RESET}_40") (pintype "bidirectional"))
    )
    (net (code "66") (name "S0_I2C_SCL") (class "Default")
      (node (ref "J1") (pin "16") (pinfunction "16_16") (pintype "passive"))
      (node (ref "R14") (pin "2") (pinfunction "2_2") (pintype "passive"))
      (node (ref "R8") (pin "1") (pinfunction "1_1") (pintype "passive"))
      (node (ref "U1") (pin "14") (pinfunction "PA09(I2C/AIN17/SER0:1+)_14") (pintype "bidirectional"))
      (node (ref "U4") (pin "6") (pinfunction "SCL_6") (pintype "bidirectional"))
    )
    (net (code "67") (name "S0_I2C_SDA") (class "Default")
      (node (ref "J1") (pin "17") (pinfunction "17_17") (pintype "passive"))
      (node (ref "R18") (pin "2") (pinfunction "2_2") (pintype "passive"))
      (node (ref "R7") (pin "1") (pinfunction "1_1") (pintype "passive"))
      (node (ref "U1") (pin "13") (pinfunction "PA08(I2C/AIN16/SER0:0+)_13") (pintype "bidirectional"))
      (node (ref "U4") (pin "5") (pinfunction "SDA_5") (pintype "bidirectional"))
    )
    (net (code "68") (name "USBN") (class "Default")
      (node (ref "D-1") (pin "X") (pinfunction "P$1_X") (pintype "passive"))
      (node (ref "D2") (pin "3") (pinfunction "3_3") (pintype "passive"))
      (node (ref "J3") (pin "2") (pinfunction "2_2") (pintype "passive"))
      (node (ref "U1") (pin "33") (pinfunction "PA24(SER3:2+)_33") (pintype "bidirectional"))
    )
    (net (code "69") (name "USBP") (class "Default")
      (node (ref "D+1") (pin "X") (pinfunction "P$1_X") (pintype "passive"))
      (node (ref "D2") (pin "2") (pinfunction "2_2") (pintype "passive"))
      (node (ref "J3") (pin "3") (pinfunction "3_3") (pintype "passive"))
      (node (ref "U1") (pin "34") (pinfunction "PA25(SER3:3+)_34") (pintype "bidirectional"))
    )
    (net (code "70") (name "VBAT_LVL") (class "Default")
      (node (ref "C33") (pin "2") (pinfunction "2_2") (pintype "passive"))
      (node (ref "R23") (pin "1") (pinfunction "1_1") (pintype "passive"))
      (node (ref "R24") (pin "2") (pinfunction "2_2") (pintype "passive"))
      (node (ref "U1") (pin "4") (pinfunction "PA03(AIN1/REFA)_4") (pintype "bidirectional"))
    )
    (net (code "71") (name "VCC") (class "Default")
      (node (ref "C10") (pin "2") (pinfunction "2_2") (pintype "passive"))
      (node (ref "C11") (pin "2") (pinfunction "2_2") (pintype "passive"))
      (node (ref "C12") (pin "1") (pinfunction "1_1") (pintype "passive"))
      (node (ref "C13") (pin "2") (pinfunction "2_2") (pintype "passive"))
      (node (ref "C14") (pin "2") (pinfunction "2_2") (pintype "passive"))
      (node (ref "C18") (pin "2") (pinfunction "2_2") (pintype "passive"))
      (node (ref "C28") (pin "2") (pinfunction "2_2") (pintype "passive"))
      (node (ref "C29") (pin "1") (pinfunction "1_1") (pintype "passive"))
      (node (ref "C30") (pin "2") (pinfunction "2_2") (pintype "passive"))
      (node (ref "C31") (pin "1") (pinfunction "1_1") (pintype "passive"))
      (node (ref "C53") (pin "1") (pinfunction "1_1") (pintype "passive"))
      (node (ref "C8") (pin "2") (pinfunction "2_2") (pintype "passive"))
      (node (ref "J1") (pin "11") (pinfunction "11_11") (pintype "passive"))
      (node (ref "J1") (pin "12") (pinfunction "12_12") (pintype "passive"))
      (node (ref "J8") (pin "1") (pinfunction "1_1") (pintype "bidirectional"))
      (node (ref "L3") (pin "1") (pinfunction "1_1") (pintype "passive"))
      (node (ref "R12") (pin "1") (pinfunction "1_1") (pintype "passive"))
      (node (ref "R27") (pin "1") (pinfunction "1_1") (pintype "passive"))
      (node (ref "R3") (pin "2") (pinfunction "2_2") (pintype "passive"))
      (node (ref "R4") (pin "2") (pinfunction "2_2") (pintype "passive"))
      (node (ref "R7") (pin "2") (pinfunction "2_2") (pintype "passive"))
      (node (ref "R8") (pin "2") (pinfunction "2_2") (pintype "passive"))
      (node (ref "U1") (pin "17") (pinfunction "VDDIO_17") (pintype "bidirectional"))
      (node (ref "U1") (pin "36") (pinfunction "VDDIO_36") (pintype "bidirectional"))
      (node (ref "U1") (pin "44") (pinfunction "VDDIN_44") (pintype "bidirectional"))
      (node (ref "U18") (pin "1") (pinfunction "OUT_1") (pintype "power_in"))
      (node (ref "U3") (pin "10") (pinfunction "VCC_10") (pintype "bidirectional"))
      (node (ref "U3") (pin "9") (pinfunction "VCC_IO_9") (pintype "bidirectional"))
      (node (ref "U4") (pin "8") (pinfunction "VCC_8") (pintype "bidirectional"))
    )
    (net (code "72") (name "V_BATT") (class "Default")
      (node (ref "C19") (pin "2") (pinfunction "2_2") (pintype "passive"))
      (node (ref "C7") (pin "2") (pinfunction "2_2") (pintype "passive"))
      (node (ref "R23") (pin "2") (pinfunction "2_2") (pintype "passive"))
      (node (ref "S1") (pin "3") (pinfunction "3_3") (pintype "bidirectional"))
      (node (ref "S1") (pin "6") (pinfunction "6_6") (pintype "bidirectional"))
      (node (ref "U18") (pin "4") (pinfunction "EN_4") (pintype "input"))
      (node (ref "U18") (pin "6") (pinfunction "IN_6") (pintype "power_in"))
      (node (ref "U9") (pin "4") (pinfunction "EN_4") (pintype "input"))
      (node (ref "U9") (pin "6") (pinfunction "IN_6") (pintype "power_in"))
    )
    (net (code "73") (name "_V_BATT") (class "Default")
      (node (ref "C17") (pin "1") (pinfunction "+_1") (pintype "bidirectional"))
      (node (ref "J6") (pin "1") (pinfunction "2_1") (pintype "passive"))
      (node (ref "S1") (pin "2") (pinfunction "2_2") (pintype "bidirectional"))
      (node (ref "S1") (pin "5") (pinfunction "5_5") (pintype "bidirectional"))
      (node (ref "U5") (pin "3") (pinfunction "VBAT_3") (pintype "bidirectional"))
    )
    (net (code "74") (name "unconnected-(J1-Pad1)") (class "Default")
      (node (ref "J1") (pin "1") (pinfunction "1_1") (pintype "passive"))
    )
    (net (code "75") (name "unconnected-(J1-PadMP1)") (class "Default")
      (node (ref "J1") (pin "MP1") (pinfunction "MP1_MP1") (pintype "passive"))
    )
    (net (code "76") (name "unconnected-(J1-PadMP2)") (class "Default")
      (node (ref "J1") (pin "MP2") (pinfunction "MP2_MP2") (pintype "passive"))
    )
    (net (code "77") (name "unconnected-(J8-Pad6)") (class "Default")
      (node (ref "J8") (pin "6") (pinfunction "6_6") (pintype "bidirectional"))
    )
    (net (code "78") (name "unconnected-(S1-Pad1)") (class "Default")
      (node (ref "S1") (pin "1") (pinfunction "1_1") (pintype "bidirectional"))
    )
    (net (code "79") (name "unconnected-(S1-Pad4)") (class "Default")
      (node (ref "S1") (pin "4") (pinfunction "4_4") (pintype "bidirectional"))
    )
    (net (code "80") (name "unconnected-(U1-PA05(AIN5{slash}SER0:1{slash}TC0:1)-Pad10)") (class "Default")
      (node (ref "U1") (pin "10") (pinfunction "PA05(AIN5/SER0:1/TC0:1)_10") (pintype "bidirectional"))
    )
    (net (code "81") (name "unconnected-(U1-PA07(AIN7{slash}SER0:3{slash}TC1:1)-Pad12)") (class "Default")
      (node (ref "U1") (pin "12") (pinfunction "PA07(AIN7/SER0:3/TC1:1)_12") (pintype "bidirectional"))
    )
    (net (code "82") (name "unconnected-(U1-PA11(AIN19{slash}SER0:3+)-Pad16)") (class "Default")
      (node (ref "U1") (pin "16") (pinfunction "PA11(AIN19/SER0:3+)_16") (pintype "bidirectional"))
    )
    (net (code "83") (name "unconnected-(U1-PA21(SER5:3+)-Pad30)") (class "Default")
      (node (ref "U1") (pin "30") (pinfunction "PA21(SER5:3+)_30") (pintype "bidirectional"))
    )
    (net (code "84") (name "unconnected-(U1-PA22(I2C{slash}SER3:0+)-Pad31)") (class "Default")
      (node (ref "U1") (pin "31") (pinfunction "PA22(I2C/SER3:0+)_31") (pintype "bidirectional"))
    )
    (net (code "85") (name "unconnected-(U1-PB02(AIN10{slash}SER5:0)-Pad47)") (class "Default")
      (node (ref "U1") (pin "47") (pinfunction "PB02(AIN10/SER5:0)_47") (pintype "bidirectional"))
    )
    (net (code "86") (name "unconnected-(U3-ANT-Pad13)") (class "Default")
      (node (ref "U3") (pin "13") (pinfunction "ANT_13") (pintype "bidirectional"))
    )
    (net (code "87") (name "unconnected-(U3-GPIO_25{slash}_RMII_MDCLK{slash}-Pad25)") (class "Default")
      (node (ref "U3") (pin "25") (pinfunction "GPIO_25/_RMII_MDCLK/_25") (pintype "bidirectional"))
    )
    (net (code "88") (name "unconnected-(U3-GPI_2{slash}_ADC_2-Pad2)") (class "Default")
      (node (ref "U3") (pin "2") (pinfunction "GPI_2/_ADC_2_2") (pintype "bidirectional"))
    )
    (net (code "89") (name "unconnected-(U3-GPI_3{slash}_ADC_3-Pad3)") (class "Default")
      (node (ref "U3") (pin "3") (pinfunction "GPI_3/_ADC_3_3") (pintype "bidirectional"))
    )
    (net (code "90") (name "unconnected-(U3-GPI_4{slash}_ADC_4-Pad4)") (class "Default")
      (node (ref "U3") (pin "4") (pinfunction "GPI_4/_ADC_4_4") (pintype "bidirectional"))
    )
    (net (code "91") (name "unconnected-(U3-GPI_34{slash}_ADC_3-Pad34)") (class "Default")
      (node (ref "U3") (pin "34") (pinfunction "GPI_34/_ADC_3_34") (pintype "bidirectional"))
    )
    (net (code "92") (name "unconnected-(U3-RSVD_1-Pad11)") (class "Default")
      (node (ref "U3") (pin "11") (pinfunction "RSVD_1_11") (pintype "bidirectional"))
    )
    (net (code "93") (name "unconnected-(U3-RSVD_2-Pad15)") (class "Default")
      (node (ref "U3") (pin "15") (pinfunction "RSVD_2_15") (pintype "bidirectional"))
    )
    (net (code "94") (name "unconnected-(U3-RSVD_3-Pad33)") (class "Default")
      (node (ref "U3") (pin "33") (pinfunction "RSVD_3_33") (pintype "bidirectional"))
    )
    (net (code "95") (name "unconnected-(U4-EP-Pad9)") (class "Default")
      (node (ref "U4") (pin "9") (pinfunction "EP_9") (pintype "bidirectional"))
    )
    (net (code "96") (name "unconnected-(U4-NC_1-Pad1)") (class "Default")
      (node (ref "U4") (pin "1") (pinfunction "NC_1_1") (pintype "bidirectional"))
    )
    (net (code "97") (name "unconnected-(U4-NC_2-Pad2)") (class "Default")
      (node (ref "U4") (pin "2") (pinfunction "NC_2_2") (pintype "bidirectional"))
    )
    (net (code "98") (name "unconnected-(U4-NC_3-Pad3)") (class "Default")
      (node (ref "U4") (pin "3") (pinfunction "NC_3_3") (pintype "bidirectional"))
    )
    (net (code "99") (name "unconnected-(U4-NC_4-Pad7)") (class "Default")
      (node (ref "U4") (pin "7") (pinfunction "NC_4_7") (pintype "bidirectional"))
    )
    (net (code "100") (name "unconnected-(U8-NC-Pad4)") (class "Default")
      (node (ref "U8") (pin "4") (pinfunction "NC_4") (pintype "no_connect"))
    )
  )
)
